# 7_Current_Sensing.net
KiCad netlist of a schematic drawn in Altium Designer
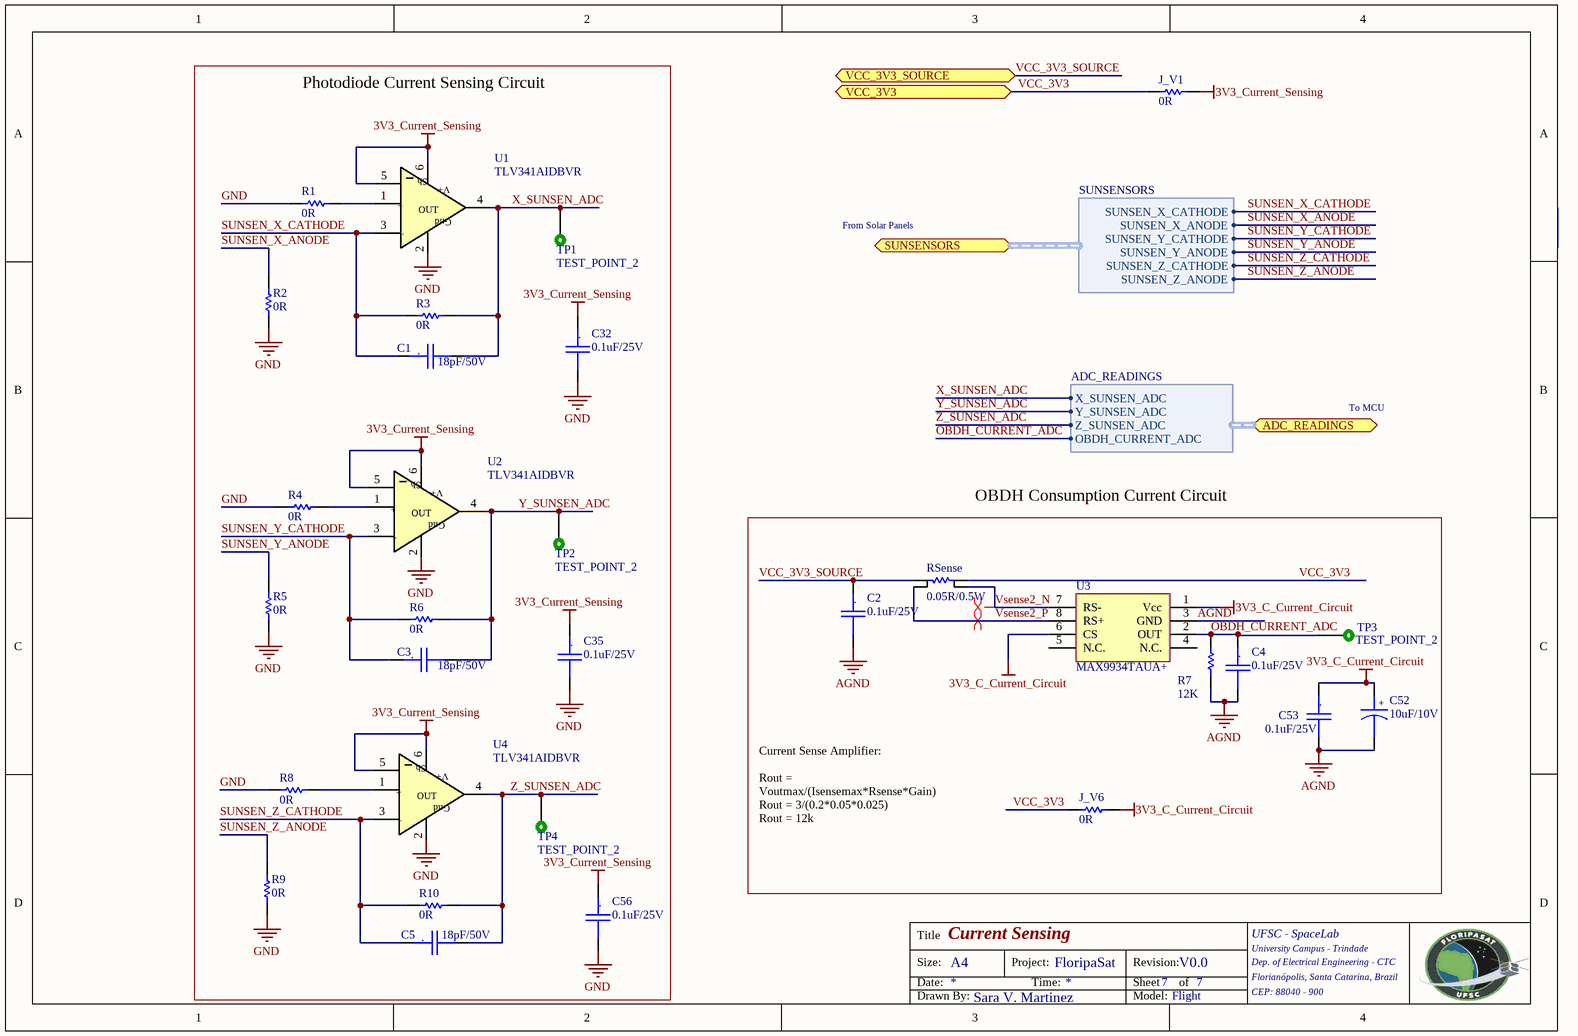
[diagram p0: 7_Current_Sensing.SchDoc]

(export (version "E")
  (design (tool "Eeschema 10.0.6"))
  (components
    (comp (ref "C1")
      (value "18pF/50V")
      (footprint "CC0805")
      (description "CAP CER 18pF 50V 5% X7R 0805")
      (fields (field (name "PARTNUMBER") "CC0805JRNPO9BN180"))
      (libsource (lib "FloripaSatSchlib") (part "Cap_Cer_X7R_18pF_50V_0805"))
    )
    (comp (ref "C2")
      (value "0.1uF/25V")
      (footprint "CC0805")
      (description "CAP CER 0.1UF 25V 10% X7R 0805")
      (fields (field (name "PARTNUMBER") "CC0805KRX7R8BB104"))
      (libsource (lib "FloripaSatSchlib") (part "Cap_Cer_X7R_0.1uF_25V_0805"))
    )
    (comp (ref "C3")
      (value "18pF/50V")
      (footprint "CC0805")
      (description "CAP CER 18pF 50V 5% X7R 0805")
      (fields (field (name "PARTNUMBER") "CC0805JRNPO9BN180"))
      (libsource (lib "FloripaSatSchlib") (part "Cap_Cer_X7R_18pF_50V_0805"))
    )
    (comp (ref "C4")
      (value "0.1uF/25V")
      (footprint "CC0805")
      (description "CAP CER 0.1UF 25V 10% X7R 0805")
      (fields (field (name "PARTNUMBER") "CC0805KRX7R8BB104"))
      (libsource (lib "FloripaSatSchlib") (part "Cap_Cer_X7R_0.1uF_25V_0805"))
    )
    (comp (ref "C5")
      (value "18pF/50V")
      (footprint "CC0805")
      (description "CAP CER 18pF 50V 5% X7R 0805")
      (fields (field (name "PARTNUMBER") "CC0805JRNPO9BN180"))
      (libsource (lib "FloripaSatSchlib") (part "Cap_Cer_X7R_18pF_50V_0805"))
    )
    (comp (ref "C32")
      (value "0.1uF/25V")
      (footprint "CC0805")
      (description "CAP CER 0.1UF 25V 10% X7R 0805")
      (fields (field (name "PARTNUMBER") "CC0805KRX7R8BB104"))
      (libsource (lib "FloripaSatSchlib") (part "Cap_Cer_X7R_0.1uF_25V_0805"))
    )
    (comp (ref "C35")
      (value "0.1uF/25V")
      (footprint "CC0805")
      (description "CAP CER 0.1UF 25V 10% X7R 0805")
      (fields (field (name "PARTNUMBER") "CC0805KRX7R8BB104"))
      (libsource (lib "FloripaSatSchlib") (part "Cap_Cer_X7R_0.1uF_25V_0805"))
    )
    (comp (ref "C52")
      (value "10uF/10V")
      (footprint "FloripaSatPcbLib:CC0805_Tantalum")
      (description "CAP Tantalum 10uF 10V 20% 0805")
      (fields (field (name "PARTNUMBER") "TPSP106M010R2000"))
      (libsource (lib "FloripaSatSchlib") (part "Cap_Tant_SMD_10uF_10V_0805"))
    )
    (comp (ref "C53")
      (value "0.1uF/25V")
      (footprint "CC0805")
      (description "CAP CER 0.1UF 25V 10% X7R 0805")
      (fields (field (name "PARTNUMBER") "CC0805KRX7R8BB104"))
      (libsource (lib "FloripaSatSchlib") (part "Cap_Cer_X7R_0.1uF_25V_0805"))
    )
    (comp (ref "C56")
      (value "0.1uF/25V")
      (footprint "CC0805")
      (description "CAP CER 0.1UF 25V 10% X7R 0805")
      (fields (field (name "PARTNUMBER") "CC0805KRX7R8BB104"))
      (libsource (lib "FloripaSatSchlib") (part "Cap_Cer_X7R_0.1uF_25V_0805"))
    )
    (comp (ref "J_V1")
      (value "0R")
      (footprint "FloripaSatPcbLib:0805")
      (description "RES 0R OHM 1/16W JUMPER 0805")
      (fields (field (name "PARTNUMBER") "CRCW08050000Z0EA"))
      (libsource (lib "FloripaSatSchlib") (part "R0R_JUMPER_1/16W_0805"))
    )
    (comp (ref "J_V6")
      (value "0R")
      (footprint "FloripaSatPcbLib:0805")
      (description "RES 0R OHM 1/16W JUMPER 0805")
      (fields (field (name "PARTNUMBER") "CRCW08050000Z0EA"))
      (libsource (lib "FloripaSatSchlib") (part "R0R_JUMPER_1/16W_0805"))
    )
    (comp (ref "R1")
      (value "0R")
      (footprint "FloripaSatPcbLib:0805")
      (description "RES 0R OHM 1/16W JUMPER 0805")
      (fields (field (name "PARTNUMBER") "CRCW08050000Z0EA"))
      (libsource (lib "FloripaSatSchlib") (part "R0R_JUMPER_1/16W_0805"))
    )
    (comp (ref "R2")
      (value "0R")
      (footprint "FloripaSatPcbLib:0805")
      (description "RES 0R OHM 1/16W JUMPER 0805")
      (fields (field (name "PARTNUMBER") "CRCW08050000Z0EA"))
      (libsource (lib "FloripaSatSchlib") (part "R0R_JUMPER_1/16W_0805"))
    )
    (comp (ref "R3")
      (value "0R")
      (footprint "FloripaSatPcbLib:0805")
      (description "RES 0R OHM 1/16W JUMPER 0805")
      (fields (field (name "PARTNUMBER") "CRCW08050000Z0EA"))
      (libsource (lib "FloripaSatSchlib") (part "R0R_JUMPER_1/16W_0805"))
    )
    (comp (ref "R4")
      (value "0R")
      (footprint "FloripaSatPcbLib:0805")
      (description "RES 0R OHM 1/16W JUMPER 0805")
      (fields (field (name "PARTNUMBER") "CRCW08050000Z0EA"))
      (libsource (lib "FloripaSatSchlib") (part "R0R_JUMPER_1/16W_0805"))
    )
    (comp (ref "R5")
      (value "0R")
      (footprint "FloripaSatPcbLib:0805")
      (description "RES 0R OHM 1/16W JUMPER 0805")
      (fields (field (name "PARTNUMBER") "CRCW08050000Z0EA"))
      (libsource (lib "FloripaSatSchlib") (part "R0R_JUMPER_1/16W_0805"))
    )
    (comp (ref "R6")
      (value "0R")
      (footprint "FloripaSatPcbLib:0805")
      (description "RES 0R OHM 1/16W JUMPER 0805")
      (fields (field (name "PARTNUMBER") "CRCW08050000Z0EA"))
      (libsource (lib "FloripaSatSchlib") (part "R0R_JUMPER_1/16W_0805"))
    )
    (comp (ref "R7")
      (value "12K")
      (footprint "0805")
      (description "RES 1.65K OHM 1/10W 0.1% 0805")
      (fields (field (name "PARTNUMBER") "PCF0805R-1K65BT1"))
      (libsource (lib "FloripaSatSchlib") (part "R1.65K_1%_1/10W_0805"))
    )
    (comp (ref "R8")
      (value "0R")
      (footprint "FloripaSatPcbLib:0805")
      (description "RES 0R OHM 1/16W JUMPER 0805")
      (fields (field (name "PARTNUMBER") "CRCW08050000Z0EA"))
      (libsource (lib "FloripaSatSchlib") (part "R0R_JUMPER_1/16W_0805"))
    )
    (comp (ref "R9")
      (value "0R")
      (footprint "FloripaSatPcbLib:0805")
      (description "RES 0R OHM 1/16W JUMPER 0805")
      (fields (field (name "PARTNUMBER") "CRCW08050000Z0EA"))
      (libsource (lib "FloripaSatSchlib") (part "R0R_JUMPER_1/16W_0805"))
    )
    (comp (ref "R10")
      (value "0R")
      (footprint "FloripaSatPcbLib:0805")
      (description "RES 0R OHM 1/16W JUMPER 0805")
      (fields (field (name "PARTNUMBER") "CRCW08050000Z0EA"))
      (libsource (lib "FloripaSatSchlib") (part "R0R_JUMPER_1/16W_0805"))
    )
    (comp (ref "RSense")
      (value "0.05R/0.5W")
      (footprint "1206 - ohmite")
      (description "Current Sense Resistors - SMD 0.05ohm .5% 4 Terminal")
      (fields (field (name "PARTNUMBER") "LVK12R050DER"))
      (libsource (lib "FloripaSatSchlib") (part "R0.05R_0.5%_0.5W_1206"))
    )
    (comp (ref "TP1")
      (value "TEST_POINT_2")
      (footprint "TEST_POINT_2")
      (description "Test point")
      (libsource (lib "FloripaSatSchlib") (part "TEST_POINT_2"))
    )
    (comp (ref "TP2")
      (value "TEST_POINT_2")
      (footprint "TEST_POINT_2")
      (description "Test point")
      (libsource (lib "FloripaSatSchlib") (part "TEST_POINT_2"))
    )
    (comp (ref "TP3")
      (value "TEST_POINT_2")
      (footprint "TEST_POINT_2")
      (description "Test point")
      (libsource (lib "FloripaSatSchlib") (part "TEST_POINT_2"))
    )
    (comp (ref "TP4")
      (value "TEST_POINT_2")
      (footprint "TEST_POINT_2")
      (description "Test point")
      (libsource (lib "FloripaSatSchlib") (part "TEST_POINT_2"))
    )
    (comp (ref "U1")
      (value "TLV341AIDBVR")
      (footprint "SOT-23 6L")
      (libsource (lib "FloripaSatSchlib") (part "TLV341AIDBVR"))
    )
    (comp (ref "U2")
      (value "TLV341AIDBVR")
      (footprint "SOT-23 6L")
      (libsource (lib "FloripaSatSchlib") (part "TLV341AIDBVR"))
    )
    (comp (ref "U3")
      (value "MAX9934TAUA+")
      (footprint "MSOP-8")
      (libsource (lib "componentes_6_11") (part "MAX9934TAUA+"))
    )
    (comp (ref "U4")
      (value "TLV341AIDBVR")
      (footprint "SOT-23 6L")
      (libsource (lib "") (part "TLV341AIDBVR_1"))
    )
  )
  (nets
    (net (code "3") (name "/OBDH_CURRENT_ADC") (class "Default")
      (node (ref "C4") (pin "1") (pinfunction "1_1") (pintype "passive"))
      (node (ref "R7") (pin "2") (pinfunction "2_2") (pintype "passive"))
      (node (ref "TP3") (pin "1") (pinfunction "1_1") (pintype "passive"))
      (node (ref "U3") (pin "2") (pinfunction "OUT_2") (pintype "passive"))
    )
    (net (code "4") (name "/SUNSEN_X_ANODE") (class "Default")
      (node (ref "R2") (pin "2") (pinfunction "2_2") (pintype "passive"))
    )
    (net (code "5") (name "/SUNSEN_X_CATHODE") (class "Default")
      (node (ref "C1") (pin "1") (pinfunction "1_1") (pintype "passive"))
      (node (ref "R3") (pin "2") (pinfunction "2_2") (pintype "passive"))
      (node (ref "U1") (pin "3") (pinfunction "-IN_3") (pintype "passive"))
    )
    (net (code "6") (name "/SUNSEN_Y_ANODE") (class "Default")
      (node (ref "R5") (pin "2") (pinfunction "2_2") (pintype "passive"))
    )
    (net (code "7") (name "/SUNSEN_Y_CATHODE") (class "Default")
      (node (ref "C3") (pin "1") (pinfunction "1_1") (pintype "passive"))
      (node (ref "R6") (pin "2") (pinfunction "2_2") (pintype "passive"))
      (node (ref "U2") (pin "3") (pinfunction "-IN_3") (pintype "passive"))
    )
    (net (code "8") (name "/SUNSEN_Z_ANODE") (class "Default")
      (node (ref "R9") (pin "2") (pinfunction "2_2") (pintype "passive"))
    )
    (net (code "9") (name "/SUNSEN_Z_CATHODE") (class "Default")
      (node (ref "C5") (pin "1") (pinfunction "1_1") (pintype "passive"))
      (node (ref "R10") (pin "2") (pinfunction "2_2") (pintype "passive"))
      (node (ref "U4") (pin "3") (pinfunction "-IN_3") (pintype "passive"))
    )
    (net (code "10") (name "/VCC_3V3") (class "Default")
      (node (ref "J_V1") (pin "2") (pinfunction "2_2") (pintype "passive"))
      (node (ref "J_V6") (pin "2") (pinfunction "2_2") (pintype "passive"))
      (node (ref "RSense") (pin "2") (pinfunction "2_2") (pintype "passive"))
    )
    (net (code "11") (name "/VCC_3V3_SOURCE") (class "Default")
      (node (ref "C2") (pin "1") (pinfunction "1_1") (pintype "passive"))
      (node (ref "RSense") (pin "1") (pinfunction "1_1") (pintype "passive"))
    )
    (net (code "12") (name "/Vsense2_N") (class "Default")
      (node (ref "RSense") (pin "4") (pinfunction "4_4") (pintype "passive"))
      (node (ref "U3") (pin "7") (pinfunction "RS-_7") (pintype "passive"))
    )
    (net (code "13") (name "/Vsense2_P") (class "Default")
      (node (ref "RSense") (pin "3") (pinfunction "3_3") (pintype "passive"))
      (node (ref "U3") (pin "8") (pinfunction "RS+_8") (pintype "passive"))
    )
    (net (code "14") (name "/X_SUNSEN_ADC") (class "Default")
      (node (ref "C1") (pin "2") (pinfunction "2_2") (pintype "passive"))
      (node (ref "R3") (pin "1") (pinfunction "1_1") (pintype "passive"))
      (node (ref "TP1") (pin "1") (pinfunction "1_1") (pintype "passive"))
      (node (ref "U1") (pin "4") (pinfunction "OUT_4") (pintype "passive"))
    )
    (net (code "15") (name "/Y_SUNSEN_ADC") (class "Default")
      (node (ref "C3") (pin "2") (pinfunction "2_2") (pintype "passive"))
      (node (ref "R6") (pin "1") (pinfunction "1_1") (pintype "passive"))
      (node (ref "TP2") (pin "1") (pinfunction "1_1") (pintype "passive"))
      (node (ref "U2") (pin "4") (pinfunction "OUT_4") (pintype "passive"))
    )
    (net (code "16") (name "/Z_SUNSEN_ADC") (class "Default")
      (node (ref "C5") (pin "2") (pinfunction "2_2") (pintype "passive"))
      (node (ref "R10") (pin "1") (pinfunction "1_1") (pintype "passive"))
      (node (ref "TP4") (pin "1") (pinfunction "1_1") (pintype "passive"))
      (node (ref "U4") (pin "4") (pinfunction "OUT_4") (pintype "passive"))
    )
    (net (code "19") (name "3V3_C_Current_Circuit") (class "Default")
      (node (ref "C52") (pin "1") (pinfunction "1_1") (pintype "passive"))
      (node (ref "C53") (pin "1") (pinfunction "1_1") (pintype "passive"))
      (node (ref "J_V6") (pin "1") (pinfunction "1_1") (pintype "passive"))
      (node (ref "U3") (pin "1") (pinfunction "Vcc_1") (pintype "passive"))
      (node (ref "U3") (pin "6") (pinfunction "CS_6") (pintype "passive"))
    )
    (net (code "20") (name "3V3_Current_Sensing") (class "Default")
      (node (ref "C32") (pin "1") (pinfunction "1_1") (pintype "passive"))
      (node (ref "C35") (pin "1") (pinfunction "1_1") (pintype "passive"))
      (node (ref "C56") (pin "1") (pinfunction "1_1") (pintype "passive"))
      (node (ref "J_V1") (pin "1") (pinfunction "1_1") (pintype "passive"))
      (node (ref "U1") (pin "5") (pinfunction "EN_5") (pintype "passive"))
      (node (ref "U1") (pin "6") (pinfunction "V+_6") (pintype "passive"))
      (node (ref "U2") (pin "5") (pinfunction "EN_5") (pintype "passive"))
      (node (ref "U2") (pin "6") (pinfunction "V+_6") (pintype "passive"))
      (node (ref "U4") (pin "5") (pinfunction "EN_5") (pintype "passive"))
      (node (ref "U4") (pin "6") (pinfunction "V+_6") (pintype "passive"))
    )
    (net (code "21") (name "AGND") (class "Default")
      (node (ref "C2") (pin "2") (pinfunction "2_2") (pintype "passive"))
      (node (ref "C4") (pin "2") (pinfunction "2_2") (pintype "passive"))
      (node (ref "C52") (pin "2") (pinfunction "2_2") (pintype "passive"))
      (node (ref "C53") (pin "2") (pinfunction "2_2") (pintype "passive"))
      (node (ref "R7") (pin "1") (pinfunction "1_1") (pintype "passive"))
      (node (ref "U3") (pin "3") (pinfunction "GND_3") (pintype "passive"))
    )
    (net (code "22") (name "GND") (class "Default")
      (node (ref "C32") (pin "2") (pinfunction "2_2") (pintype "passive"))
      (node (ref "C35") (pin "2") (pinfunction "2_2") (pintype "passive"))
      (node (ref "C56") (pin "2") (pinfunction "2_2") (pintype "passive"))
      (node (ref "R1") (pin "2") (pinfunction "2_2") (pintype "passive"))
      (node (ref "R2") (pin "1") (pinfunction "1_1") (pintype "passive"))
      (node (ref "R4") (pin "2") (pinfunction "2_2") (pintype "passive"))
      (node (ref "R5") (pin "1") (pinfunction "1_1") (pintype "passive"))
      (node (ref "R8") (pin "2") (pinfunction "2_2") (pintype "passive"))
      (node (ref "R9") (pin "1") (pinfunction "1_1") (pintype "passive"))
      (node (ref "U1") (pin "2") (pinfunction "Gnd_2") (pintype "passive"))
      (node (ref "U2") (pin "2") (pinfunction "Gnd_2") (pintype "passive"))
      (node (ref "U4") (pin "2") (pinfunction "Gnd_2") (pintype "passive"))
    )
    (net (code "23") (name "Net-(U1-+IN)") (class "Default")
      (node (ref "R1") (pin "1") (pinfunction "1_1") (pintype "passive"))
      (node (ref "U1") (pin "1") (pinfunction "+IN_1") (pintype "passive"))
    )
    (net (code "24") (name "Net-(U2-+IN)") (class "Default")
      (node (ref "R4") (pin "1") (pinfunction "1_1") (pintype "passive"))
      (node (ref "U2") (pin "1") (pinfunction "+IN_1") (pintype "passive"))
    )
    (net (code "25") (name "Net-(U4-+IN)") (class "Default")
      (node (ref "R8") (pin "1") (pinfunction "1_1") (pintype "passive"))
      (node (ref "U4") (pin "1") (pinfunction "+IN_1") (pintype "passive"))
    )
    (net (code "26") (name "unconnected-(U3-N.C.-Pad4)") (class "Default")
      (node (ref "U3") (pin "4") (pinfunction "N.C._4") (pintype "passive"))
    )
    (net (code "27") (name "unconnected-(U3-N.C.-Pad5)") (class "Default")
      (node (ref "U3") (pin "5") (pinfunction "N.C._5") (pintype "passive"))
    )
  )
)
